# HP03S_HIH6130.net
KiCad netlist of a schematic drawn in EAGLE
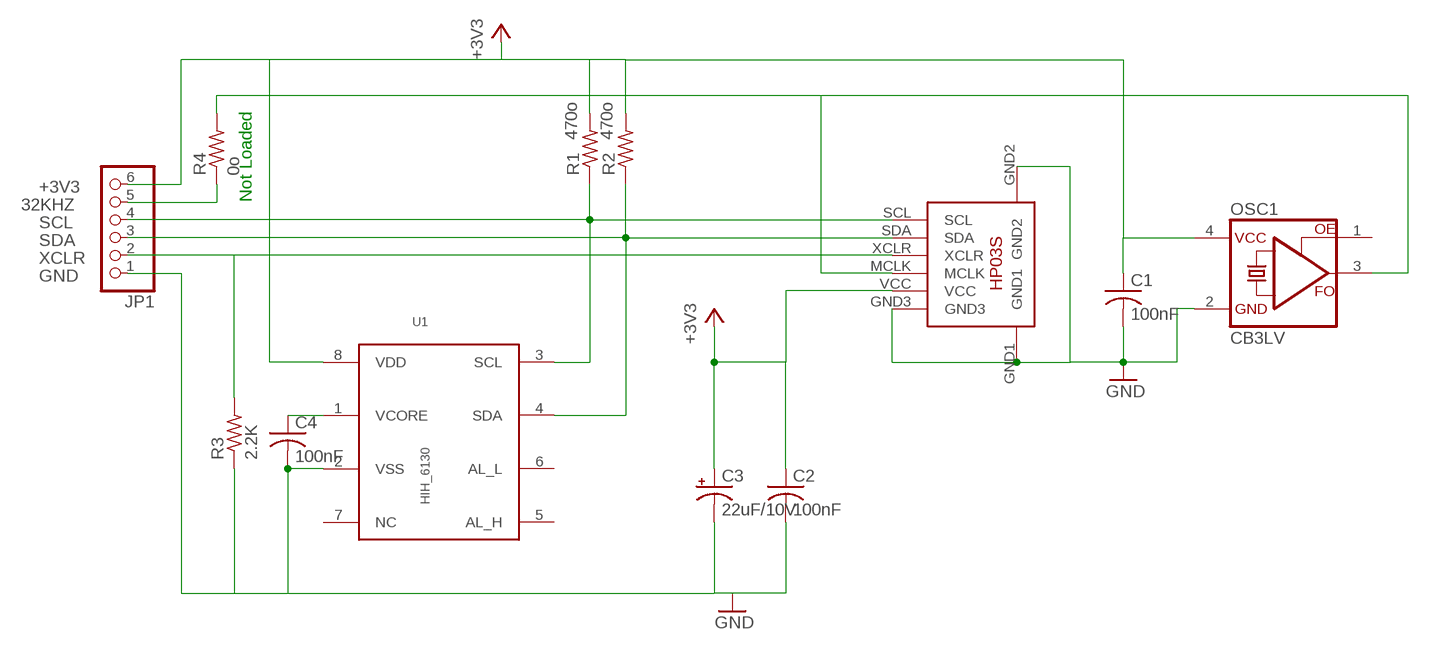
[diagram p0: schematic, sheet 1]

(export (version "E")
  (design (tool "Eeschema 10.0.6"))
  (components
    (comp (ref "C1")
      (value "100nF")
      (footprint "eagle-import:C0805")
      (libsource (lib "eagle-import") (part "C-USC0805"))
    )
    (comp (ref "C2")
      (value "100nF")
      (footprint "eagle-import:C0805K")
      (libsource (lib "eagle-import") (part "C-USC0805K"))
    )
    (comp (ref "C3")
      (value "22uF/10V")
      (footprint "eagle-import:SMC_B")
      (libsource (lib "eagle-import") (part "CPOL-USSMCB"))
    )
    (comp (ref "C4")
      (value "100nF")
      (footprint "eagle-import:C0805K")
      (libsource (lib "eagle-import") (part "C-USC0805K"))
    )
    (comp (ref "JP1")
      (value "PINHD-1X6")
      (footprint "eagle-import:1X06")
      (libsource (lib "eagle-import") (part "PINHD-1X6"))
    )
    (comp (ref "OSC1")
      (value "CB3LV")
      (footprint "eagle-import:SMD7.5X5MM")
      (libsource (lib "eagle-import") (part "CB3LV"))
    )
    (comp (ref "R1")
      (value "470o")
      (footprint "eagle-import:R0603")
      (libsource (lib "eagle-import") (part "R-US_R0603"))
    )
    (comp (ref "R2")
      (value "470o")
      (footprint "eagle-import:R0603")
      (libsource (lib "eagle-import") (part "R-US_R0603"))
    )
    (comp (ref "R3")
      (value "2.2K")
      (footprint "eagle-import:R0603")
      (libsource (lib "eagle-import") (part "R-US_R0603"))
    )
    (comp (ref "R4")
      (value "0o")
      (footprint "eagle-import:R0603")
      (libsource (lib "eagle-import") (part "R-US_R0603"))
    )
    (comp (ref "U1")
      (value "HIH_6130")
      (footprint "eagle-import:SOIC8")
      (libsource (lib "eagle-import") (part "HIH_6130"))
    )
    (comp (ref "U2")
      (value "HP03S")
      (footprint "eagle-import:HP03S")
      (libsource (lib "eagle-import") (part "HP03S"))
    )
  )
  (nets
    (net (code "1") (name "+3V3") (class "Default")
      (node (ref "C1") (pin "1") (pinfunction "1_1") (pintype "passive"))
      (node (ref "C2") (pin "1") (pinfunction "1_1") (pintype "passive"))
      (node (ref "C3") (pin "+") (pinfunction "+_+") (pintype "passive"))
      (node (ref "JP1") (pin "6") (pinfunction "6_6") (pintype "passive"))
      (node (ref "OSC1") (pin "4") (pinfunction "VCC_4") (pintype "power_in"))
      (node (ref "R1") (pin "2") (pinfunction "2_2") (pintype "passive"))
      (node (ref "R2") (pin "2") (pinfunction "2_2") (pintype "passive"))
      (node (ref "U1") (pin "8") (pinfunction "VDD_8") (pintype "bidirectional"))
      (node (ref "U2") (pin "VCC") (pinfunction "VCC_VCC") (pintype "bidirectional"))
    )
    (net (code "2") (name "/32KHZ") (class "Default")
      (node (ref "JP1") (pin "5") (pinfunction "5_5") (pintype "passive"))
      (node (ref "R4") (pin "1") (pinfunction "1_1") (pintype "passive"))
    )
    (net (code "3") (name "/SCL") (class "Default")
      (node (ref "JP1") (pin "4") (pinfunction "4_4") (pintype "passive"))
      (node (ref "R1") (pin "1") (pinfunction "1_1") (pintype "passive"))
      (node (ref "U1") (pin "3") (pinfunction "SCL_3") (pintype "bidirectional"))
      (node (ref "U2") (pin "SCL") (pinfunction "SCL_SCL") (pintype "bidirectional"))
    )
    (net (code "4") (name "/SDA") (class "Default")
      (node (ref "JP1") (pin "3") (pinfunction "3_3") (pintype "passive"))
      (node (ref "R2") (pin "1") (pinfunction "1_1") (pintype "passive"))
      (node (ref "U1") (pin "4") (pinfunction "SDA_4") (pintype "bidirectional"))
      (node (ref "U2") (pin "SDA") (pinfunction "SDA_SDA") (pintype "bidirectional"))
    )
    (net (code "5") (name "/XCLR") (class "Default")
      (node (ref "JP1") (pin "2") (pinfunction "2_2") (pintype "passive"))
      (node (ref "R3") (pin "2") (pinfunction "2_2") (pintype "passive"))
      (node (ref "U2") (pin "XCLR") (pinfunction "XCLR_XCLR") (pintype "bidirectional"))
    )
    (net (code "6") (name "GND") (class "Default")
      (node (ref "C1") (pin "2") (pinfunction "2_2") (pintype "passive"))
      (node (ref "C2") (pin "2") (pinfunction "2_2") (pintype "passive"))
      (node (ref "C3") (pin "-") (pinfunction "-_-") (pintype "passive"))
      (node (ref "C4") (pin "2") (pinfunction "2_2") (pintype "passive"))
      (node (ref "JP1") (pin "1") (pinfunction "1_1") (pintype "passive"))
      (node (ref "OSC1") (pin "2") (pinfunction "GND_2") (pintype "power_in"))
      (node (ref "R3") (pin "1") (pinfunction "1_1") (pintype "passive"))
      (node (ref "U1") (pin "2") (pinfunction "VSS_2") (pintype "bidirectional"))
      (node (ref "U2") (pin "GND1") (pinfunction "GND1_GND1") (pintype "bidirectional"))
      (node (ref "U2") (pin "GND2") (pinfunction "GND2_GND2") (pintype "bidirectional"))
      (node (ref "U2") (pin "GND3") (pinfunction "GND3_GND3") (pintype "bidirectional"))
    )
    (net (code "7") (name "Net-(OSC1-FO)") (class "Default")
      (node (ref "OSC1") (pin "3") (pinfunction "FO_3") (pintype "output"))
      (node (ref "R4") (pin "2") (pinfunction "2_2") (pintype "passive"))
      (node (ref "U2") (pin "MCLK") (pinfunction "MCLK_MCLK") (pintype "bidirectional"))
    )
    (net (code "8") (name "Net-(U1-VCORE)") (class "Default")
      (node (ref "C4") (pin "1") (pinfunction "1_1") (pintype "passive"))
      (node (ref "U1") (pin "1") (pinfunction "VCORE_1") (pintype "bidirectional"))
    )
    (net (code "9") (name "unconnected-(OSC1-OE-Pad1)") (class "Default")
      (node (ref "OSC1") (pin "1") (pinfunction "OE_1") (pintype "input"))
    )
    (net (code "10") (name "unconnected-(U1-AL_H-Pad5)") (class "Default")
      (node (ref "U1") (pin "5") (pinfunction "AL_H_5") (pintype "bidirectional"))
    )
    (net (code "11") (name "unconnected-(U1-AL_L-Pad6)") (class "Default")
      (node (ref "U1") (pin "6") (pinfunction "AL_L_6") (pintype "bidirectional"))
    )
    (net (code "12") (name "unconnected-(U1-NC-Pad7)") (class "Default")
      (node (ref "U1") (pin "7") (pinfunction "NC_7") (pintype "bidirectional"))
    )
  )
)
